# untitled.net
KiCad netlist of a schematic drawn in EAGLE
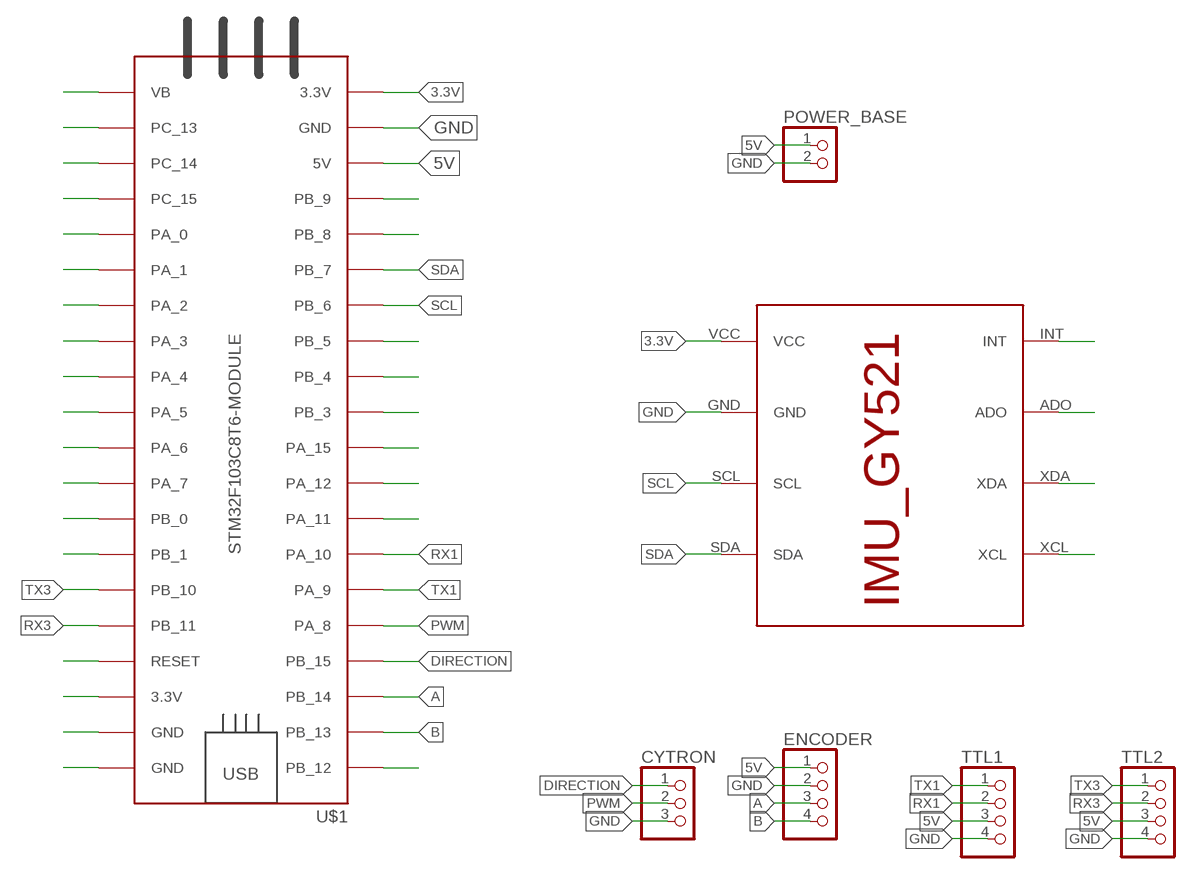
[diagram p0: schematic, sheet 1]

(export (version "E")
  (design (tool "Eeschema 10.0.6"))
  (components
    (comp (ref "CYTRON")
      (value "PINHD-1X3")
      (footprint "eagle-import:1X03")
      (libsource (lib "eagle-import") (part "PINHD-1X3"))
    )
    (comp (ref "ENCODER")
      (value "PINHD-1X4")
      (footprint "eagle-import:1X04")
      (libsource (lib "eagle-import") (part "PINHD-1X4"))
    )
    (comp (ref "POWER_BASE")
      (value "PINHD-2_DATA")
      (footprint "eagle-import:1X02_DATA")
      (libsource (lib "eagle-import") (part "PINHD-2_DATA"))
    )
    (comp (ref "TTL1")
      (value "PINHD-1X4")
      (footprint "eagle-import:1X04")
      (libsource (lib "eagle-import") (part "PINHD-1X4"))
    )
    (comp (ref "TTL2")
      (value "PINHD-1X4")
      (footprint "eagle-import:1X04")
      (libsource (lib "eagle-import") (part "PINHD-1X4"))
    )
    (comp (ref "U$1")
      (value "STM32F103C8T6-MODULE")
      (footprint "eagle-import:STM32F103C8T6-MODULE")
      (libsource (lib "eagle-import") (part "STM32F103C8T6-MODULE"))
    )
    (comp (ref "U$2")
      (value "IMU_ROBOCON_GY521")
      (footprint "eagle-import:IMU_GY521")
      (libsource (lib "eagle-import") (part "IMU_ROBOCON_GY521"))
    )
  )
  (nets
    (net (code "1") (name "3.3V") (class "Default")
      (node (ref "U$1") (pin "3.3V_1") (pinfunction "3.3V_3.3V_1") (pintype "bidirectional"))
      (node (ref "U$1") (pin "3.3V_2") (pinfunction "3.3V_3.3V_2") (pintype "bidirectional"))
      (node (ref "U$2") (pin "VCC") (pinfunction "VCC_VCC") (pintype "bidirectional"))
    )
    (net (code "2") (name "5V") (class "Default")
      (node (ref "ENCODER") (pin "1") (pinfunction "1_1") (pintype "passive"))
      (node (ref "POWER_BASE") (pin "1") (pinfunction "1_1") (pintype "passive"))
      (node (ref "TTL1") (pin "3") (pinfunction "3_3") (pintype "passive"))
      (node (ref "TTL2") (pin "3") (pinfunction "3_3") (pintype "passive"))
      (node (ref "U$1") (pin "5V") (pinfunction "5V_5V") (pintype "bidirectional"))
    )
    (net (code "3") (name "A") (class "Default")
      (node (ref "ENCODER") (pin "3") (pinfunction "3_3") (pintype "passive"))
      (node (ref "U$1") (pin "PB_14") (pinfunction "PB_14_PB_14") (pintype "bidirectional"))
    )
    (net (code "4") (name "B") (class "Default")
      (node (ref "ENCODER") (pin "4") (pinfunction "4_4") (pintype "passive"))
      (node (ref "U$1") (pin "PB_13") (pinfunction "PB_13_PB_13") (pintype "bidirectional"))
    )
    (net (code "5") (name "DIRECTION") (class "Default")
      (node (ref "CYTRON") (pin "1") (pinfunction "1_1") (pintype "passive"))
      (node (ref "U$1") (pin "PB_15") (pinfunction "PB_15_PB_15") (pintype "bidirectional"))
    )
    (net (code "6") (name "GND") (class "Default")
      (node (ref "CYTRON") (pin "3") (pinfunction "3_3") (pintype "passive"))
      (node (ref "ENCODER") (pin "2") (pinfunction "2_2") (pintype "passive"))
      (node (ref "POWER_BASE") (pin "2") (pinfunction "2_2") (pintype "passive"))
      (node (ref "TTL1") (pin "4") (pinfunction "4_4") (pintype "passive"))
      (node (ref "TTL2") (pin "4") (pinfunction "4_4") (pintype "passive"))
      (node (ref "U$1") (pin "GND_1") (pinfunction "GND_GND_1") (pintype "bidirectional"))
      (node (ref "U$1") (pin "GND_2") (pinfunction "GND_GND_2") (pintype "bidirectional"))
      (node (ref "U$1") (pin "GND_3") (pinfunction "GND_GND_3") (pintype "power_in"))
      (node (ref "U$2") (pin "GND") (pinfunction "GND_GND") (pintype "bidirectional"))
    )
    (net (code "7") (name "PWM") (class "Default")
      (node (ref "CYTRON") (pin "2") (pinfunction "2_2") (pintype "passive"))
      (node (ref "U$1") (pin "PA_8") (pinfunction "PA_8_PA_8") (pintype "bidirectional"))
    )
    (net (code "8") (name "RX1") (class "Default")
      (node (ref "TTL1") (pin "2") (pinfunction "2_2") (pintype "passive"))
      (node (ref "U$1") (pin "PA_10") (pinfunction "PA_10_PA_10") (pintype "bidirectional"))
    )
    (net (code "9") (name "RX3") (class "Default")
      (node (ref "TTL2") (pin "2") (pinfunction "2_2") (pintype "passive"))
      (node (ref "U$1") (pin "PB_11") (pinfunction "PB_11_PB_11") (pintype "bidirectional"))
    )
    (net (code "10") (name "SCL") (class "Default")
      (node (ref "U$1") (pin "PB_6") (pinfunction "PB_6_PB_6") (pintype "bidirectional"))
      (node (ref "U$2") (pin "SCL") (pinfunction "SCL_SCL") (pintype "bidirectional"))
    )
    (net (code "11") (name "SDA") (class "Default")
      (node (ref "U$1") (pin "PB_7") (pinfunction "PB_7_PB_7") (pintype "bidirectional"))
      (node (ref "U$2") (pin "SDA") (pinfunction "SDA_SDA") (pintype "bidirectional"))
    )
    (net (code "12") (name "TX1") (class "Default")
      (node (ref "TTL1") (pin "1") (pinfunction "1_1") (pintype "passive"))
      (node (ref "U$1") (pin "PA_9") (pinfunction "PA_9_PA_9") (pintype "bidirectional"))
    )
    (net (code "13") (name "TX3") (class "Default")
      (node (ref "TTL2") (pin "1") (pinfunction "1_1") (pintype "passive"))
      (node (ref "U$1") (pin "PB_10") (pinfunction "PB_10_PB_10") (pintype "bidirectional"))
    )
    (net (code "14") (name "unconnected-(U$1-PadPA_0)") (class "Default")
      (node (ref "U$1") (pin "PA_0") (pinfunction "PA_0_PA_0") (pintype "bidirectional"))
    )
    (net (code "15") (name "unconnected-(U$1-PadPA_1)") (class "Default")
      (node (ref "U$1") (pin "PA_1") (pinfunction "PA_1_PA_1") (pintype "bidirectional"))
    )
    (net (code "16") (name "unconnected-(U$1-PadPA_2)") (class "Default")
      (node (ref "U$1") (pin "PA_2") (pinfunction "PA_2_PA_2") (pintype "bidirectional"))
    )
    (net (code "17") (name "unconnected-(U$1-PadPA_3)") (class "Default")
      (node (ref "U$1") (pin "PA_3") (pinfunction "PA_3_PA_3") (pintype "bidirectional"))
    )
    (net (code "18") (name "unconnected-(U$1-PadPA_4)") (class "Default")
      (node (ref "U$1") (pin "PA_4") (pinfunction "PA_4_PA_4") (pintype "bidirectional"))
    )
    (net (code "19") (name "unconnected-(U$1-PadPA_5)") (class "Default")
      (node (ref "U$1") (pin "PA_5") (pinfunction "PA_5_PA_5") (pintype "bidirectional"))
    )
    (net (code "20") (name "unconnected-(U$1-PadPA_6)") (class "Default")
      (node (ref "U$1") (pin "PA_6") (pinfunction "PA_6_PA_6") (pintype "bidirectional"))
    )
    (net (code "21") (name "unconnected-(U$1-PadPA_7)") (class "Default")
      (node (ref "U$1") (pin "PA_7") (pinfunction "PA_7_PA_7") (pintype "bidirectional"))
    )
    (net (code "22") (name "unconnected-(U$1-PadPA_11)") (class "Default")
      (node (ref "U$1") (pin "PA_11") (pinfunction "PA_11_PA_11") (pintype "bidirectional"))
    )
    (net (code "23") (name "unconnected-(U$1-PadPA_12)") (class "Default")
      (node (ref "U$1") (pin "PA_12") (pinfunction "PA_12_PA_12") (pintype "bidirectional"))
    )
    (net (code "24") (name "unconnected-(U$1-PadPA_15)") (class "Default")
      (node (ref "U$1") (pin "PA_15") (pinfunction "PA_15_PA_15") (pintype "bidirectional"))
    )
    (net (code "25") (name "unconnected-(U$1-PadPB_0)") (class "Default")
      (node (ref "U$1") (pin "PB_0") (pinfunction "PB_0_PB_0") (pintype "bidirectional"))
    )
    (net (code "26") (name "unconnected-(U$1-PadPB_1)") (class "Default")
      (node (ref "U$1") (pin "PB_1") (pinfunction "PB_1_PB_1") (pintype "bidirectional"))
    )
    (net (code "27") (name "unconnected-(U$1-PadPB_3)") (class "Default")
      (node (ref "U$1") (pin "PB_3") (pinfunction "PB_3_PB_3") (pintype "bidirectional"))
    )
    (net (code "28") (name "unconnected-(U$1-PadPB_4)") (class "Default")
      (node (ref "U$1") (pin "PB_4") (pinfunction "PB_4_PB_4") (pintype "bidirectional"))
    )
    (net (code "29") (name "unconnected-(U$1-PadPB_5)") (class "Default")
      (node (ref "U$1") (pin "PB_5") (pinfunction "PB_5_PB_5") (pintype "bidirectional"))
    )
    (net (code "30") (name "unconnected-(U$1-PadPB_8)") (class "Default")
      (node (ref "U$1") (pin "PB_8") (pinfunction "PB_8_PB_8") (pintype "bidirectional"))
    )
    (net (code "31") (name "unconnected-(U$1-PadPB_9)") (class "Default")
      (node (ref "U$1") (pin "PB_9") (pinfunction "PB_9_PB_9") (pintype "bidirectional"))
    )
    (net (code "32") (name "unconnected-(U$1-PadPB_12)") (class "Default")
      (node (ref "U$1") (pin "PB_12") (pinfunction "PB_12_PB_12") (pintype "bidirectional"))
    )
    (net (code "33") (name "unconnected-(U$1-PadPC_13)") (class "Default")
      (node (ref "U$1") (pin "PC_13") (pinfunction "PC_13_PC_13") (pintype "bidirectional"))
    )
    (net (code "34") (name "unconnected-(U$1-PadPC_14)") (class "Default")
      (node (ref "U$1") (pin "PC_14") (pinfunction "PC_14_PC_14") (pintype "bidirectional"))
    )
    (net (code "35") (name "unconnected-(U$1-PadPC_15)") (class "Default")
      (node (ref "U$1") (pin "PC_15") (pinfunction "PC_15_PC_15") (pintype "bidirectional"))
    )
    (net (code "36") (name "unconnected-(U$1-PadRESET)") (class "Default")
      (node (ref "U$1") (pin "RESET") (pinfunction "RESET_RESET") (pintype "bidirectional"))
    )
    (net (code "37") (name "unconnected-(U$1-PadVB)") (class "Default")
      (node (ref "U$1") (pin "VB") (pinfunction "VB_VB") (pintype "bidirectional"))
    )
    (net (code "38") (name "unconnected-(U$2-PadADO)") (class "Default")
      (node (ref "U$2") (pin "ADO") (pinfunction "ADO_ADO") (pintype "bidirectional"))
    )
    (net (code "39") (name "unconnected-(U$2-PadINT)") (class "Default")
      (node (ref "U$2") (pin "INT") (pinfunction "INT_INT") (pintype "bidirectional"))
    )
    (net (code "40") (name "unconnected-(U$2-PadXCL)") (class "Default")
      (node (ref "U$2") (pin "XCL") (pinfunction "XCL_XCL") (pintype "bidirectional"))
    )
    (net (code "41") (name "unconnected-(U$2-PadXDA)") (class "Default")
      (node (ref "U$2") (pin "XDA") (pinfunction "XDA_XDA") (pintype "bidirectional"))
    )
  )
)
